# shield_v2.net
KiCad netlist of a schematic drawn in EAGLE
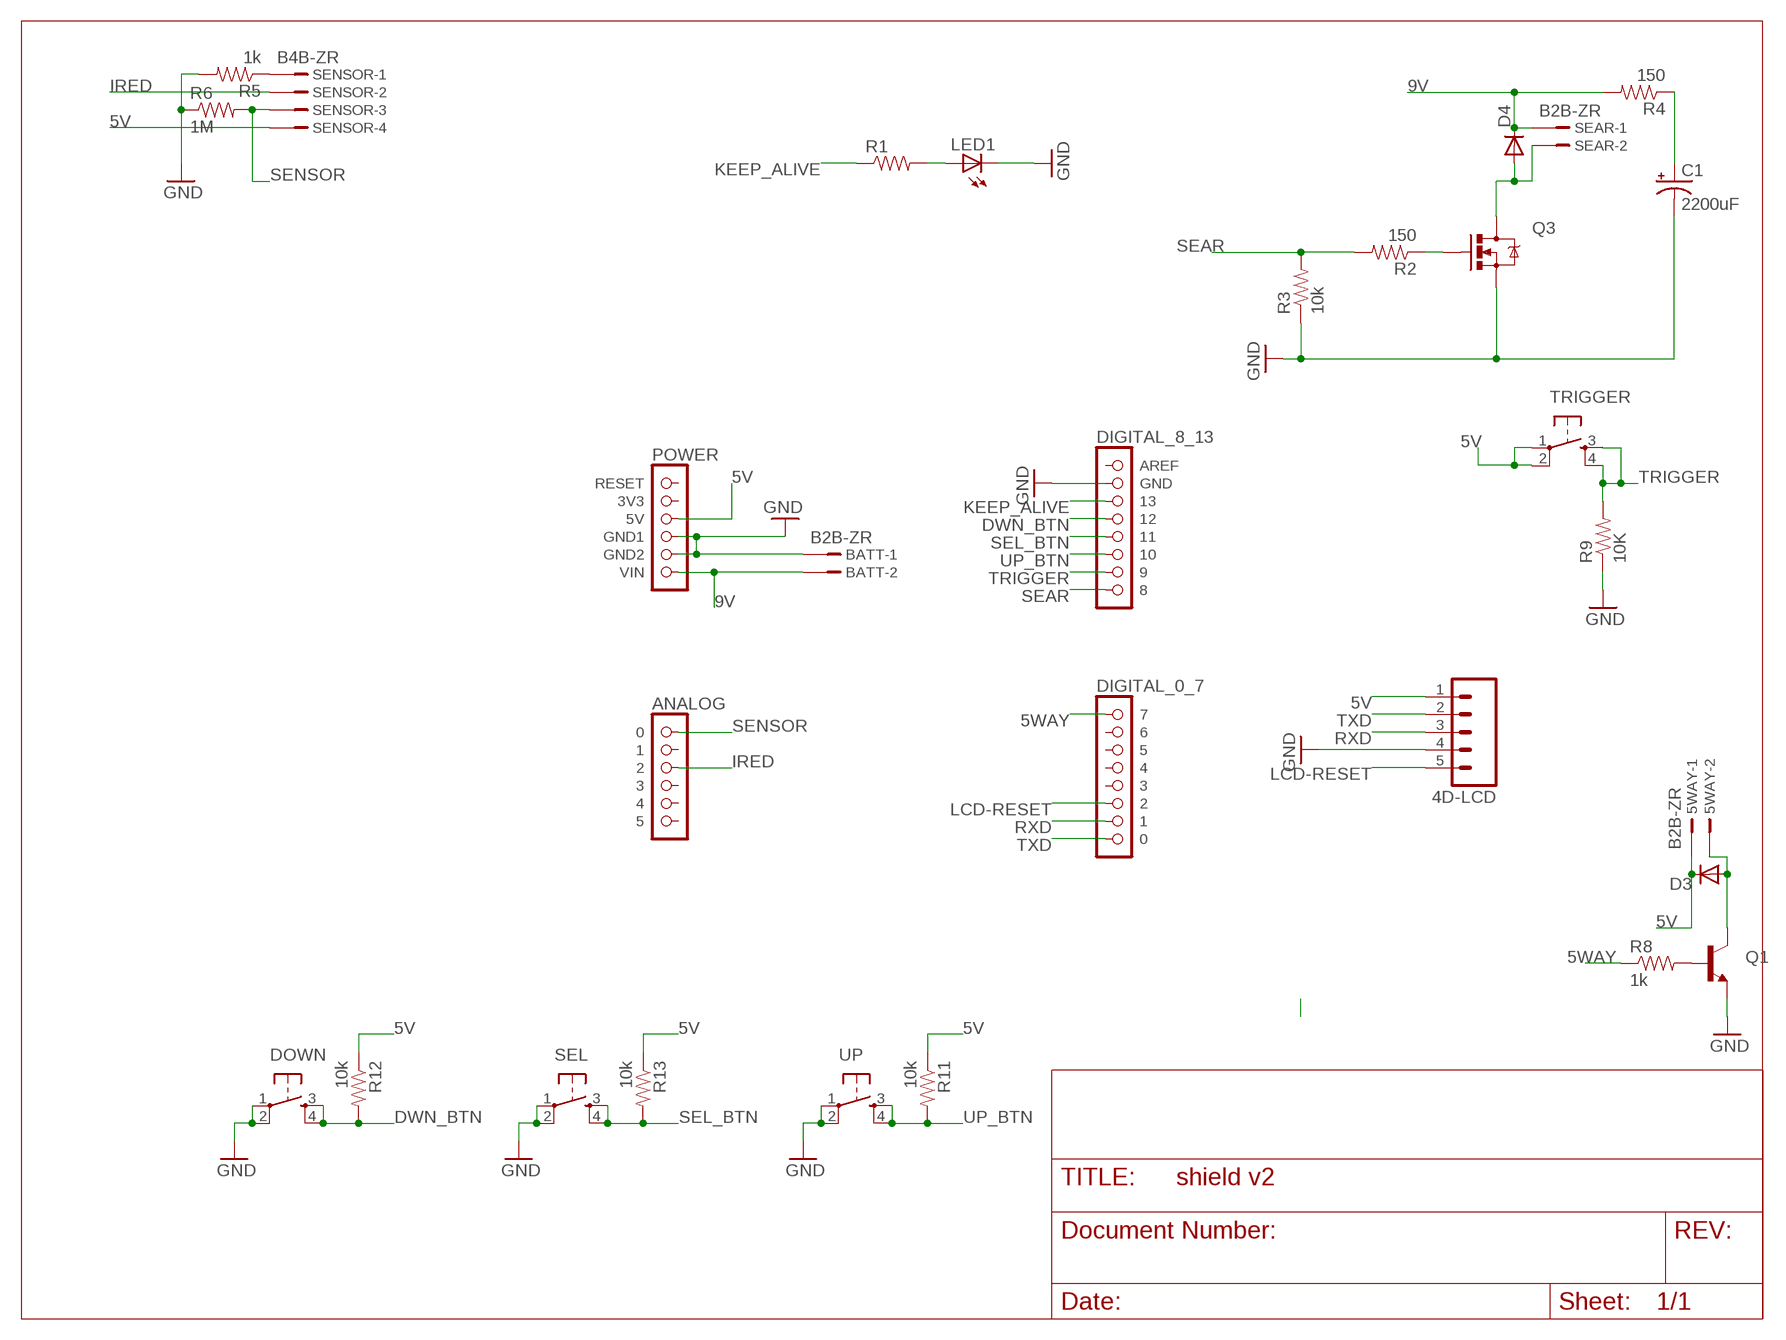
[diagram p0: schematic, sheet 1]

(export (version "E")
  (design (tool "Eeschema 10.0.6"))
  (components
    (comp (ref "4D-LCD")
      (value "M05PTH")
      (footprint "eagle-import:1X05")
      (libsource (lib "eagle-import") (part "M05PTH"))
    )
    (comp (ref "5WAY")
      (value "B2B-ZR")
      (footprint "eagle-import:B2B-ZR@1")
      (libsource (lib "eagle-import") (part "B2B-ZR"))
    )
    (comp (ref "BATT")
      (value "B2B-ZR")
      (footprint "eagle-import:B2B-ZR")
      (libsource (lib "eagle-import") (part "?2B-ZRB"))
    )
    (comp (ref "C1")
      (value "2200uF")
      (footprint "eagle-import:CPOL-RADIAL-1000UF-25V")
      (libsource (lib "eagle-import") (part "CAP_POLPTH4"))
    )
    (comp (ref "D3")
      (value "DIODEPTH")
      (footprint "eagle-import:DIODE-1N4001")
      (libsource (lib "eagle-import") (part "DIODEPTH"))
    )
    (comp (ref "D4")
      (value "DIODEPTH")
      (footprint "eagle-import:DIODE-1N4001")
      (libsource (lib "eagle-import") (part "DIODEPTH"))
    )
    (comp (ref "DOWN")
      (value "TAC_SWITCHPTH")
      (footprint "eagle-import:TACTILE-PTH")
      (libsource (lib "eagle-import") (part "TAC_SWITCHPTH"))
    )
    (comp (ref "LED1")
      (value "LED3MM")
      (footprint "eagle-import:LED3MM")
      (libsource (lib "eagle-import") (part "LED3MM"))
    )
    (comp (ref "Q1")
      (value "TRANSISTOR_NPNTO-92-AMMO")
      (footprint "eagle-import:TO-92-AMMO")
      (libsource (lib "eagle-import") (part "TRANSISTOR_NPNTO-92-AMMO"))
    )
    (comp (ref "Q3")
      (value "MOSFET-NCHANNELPTH2")
      (footprint "eagle-import:TO220V")
      (libsource (lib "eagle-import") (part "MOSFET-NCHANNELPTH2"))
    )
    (comp (ref "R1")
      (value "RESISTORPTH-1/4W")
      (footprint "eagle-import:AXIAL-0.4")
      (libsource (lib "eagle-import") (part "RESISTORPTH-1/4W"))
    )
    (comp (ref "R2")
      (value "150")
      (footprint "eagle-import:AXIAL-0.4")
      (libsource (lib "eagle-import") (part "RESISTORPTH-1/4W"))
    )
    (comp (ref "R3")
      (value "10k")
      (footprint "eagle-import:AXIAL-0.4")
      (libsource (lib "eagle-import") (part "RESISTORPTH-1/4W"))
    )
    (comp (ref "R4")
      (value "150")
      (footprint "eagle-import:AXIAL-0.4")
      (libsource (lib "eagle-import") (part "RESISTORPTH-1/4W"))
    )
    (comp (ref "R5")
      (value "1k")
      (footprint "eagle-import:AXIAL-0.4")
      (libsource (lib "eagle-import") (part "RESISTORPTH-1/4W"))
    )
    (comp (ref "R6")
      (value "1M")
      (footprint "eagle-import:AXIAL-0.4")
      (libsource (lib "eagle-import") (part "RESISTORPTH-1/4W"))
    )
    (comp (ref "R8")
      (value "1k")
      (footprint "eagle-import:AXIAL-0.4")
      (libsource (lib "eagle-import") (part "RESISTORPTH-1/4W"))
    )
    (comp (ref "R9")
      (value "10K")
      (footprint "eagle-import:AXIAL-0.4")
      (libsource (lib "eagle-import") (part "RESISTORPTH-1/4W"))
    )
    (comp (ref "R11")
      (value "10k")
      (footprint "eagle-import:AXIAL-0.4")
      (libsource (lib "eagle-import") (part "RESISTORPTH-1/4W"))
    )
    (comp (ref "R12")
      (value "10k")
      (footprint "eagle-import:AXIAL-0.4")
      (libsource (lib "eagle-import") (part "RESISTORPTH-1/4W"))
    )
    (comp (ref "R13")
      (value "10k")
      (footprint "eagle-import:AXIAL-0.4")
      (libsource (lib "eagle-import") (part "RESISTORPTH-1/4W"))
    )
    (comp (ref "SEAR")
      (value "B2B-ZR")
      (footprint "eagle-import:B2B-ZR@1")
      (libsource (lib "eagle-import") (part "B2B-ZR"))
    )
    (comp (ref "SEL")
      (value "TAC_SWITCHPTH")
      (footprint "eagle-import:TACTILE-PTH")
      (libsource (lib "eagle-import") (part "TAC_SWITCHPTH"))
    )
    (comp (ref "SENSOR")
      (value "B4B-ZR")
      (footprint "eagle-import:B4B-ZR")
      (fields (field (name "MF") "FARNELL") (field (name "MPN") "B4B-ZR(LF)(SN)"))
      (libsource (lib "eagle-import") (part "?4B-ZRB"))
    )
    (comp (ref "TRIGGER")
      (value "TAC_SWITCHPTH")
      (footprint "eagle-import:TACTILE-PTH")
      (libsource (lib "eagle-import") (part "TAC_SWITCHPTH"))
    )
    (comp (ref "U$1")
      (value "POWER")
      (footprint "eagle-import:1X06")
      (libsource (lib "eagle-import") (part "POWER"))
    )
    (comp (ref "U$2")
      (value "ANALOG")
      (footprint "eagle-import:1X06")
      (libsource (lib "eagle-import") (part "ANALOG"))
    )
    (comp (ref "U$3")
      (value "DIGITAL_0_7")
      (footprint "eagle-import:1X08")
      (libsource (lib "eagle-import") (part "DIGITAL_0_7"))
    )
    (comp (ref "U$4")
      (value "DIGITAL_8_13")
      (footprint "eagle-import:1X08")
      (libsource (lib "eagle-import") (part "DIGITAL_8_13"))
    )
    (comp (ref "UP")
      (value "TAC_SWITCHPTH")
      (footprint "eagle-import:TACTILE-PTH")
      (libsource (lib "eagle-import") (part "TAC_SWITCHPTH"))
    )
  )
  (nets
    (net (code "1") (name "/5V") (class "Default")
      (node (ref "4D-LCD") (pin "1") (pinfunction "1_1") (pintype "passive"))
      (node (ref "5WAY") (pin "1") (pinfunction "1_1") (pintype "passive"))
      (node (ref "D3") (pin "C") (pinfunction "C_C") (pintype "passive"))
      (node (ref "R11") (pin "P$1") (pinfunction "1_P$1") (pintype "passive"))
      (node (ref "R12") (pin "P$1") (pinfunction "1_P$1") (pintype "passive"))
      (node (ref "R13") (pin "P$1") (pinfunction "1_P$1") (pintype "passive"))
      (node (ref "SENSOR") (pin "4") (pinfunction "1_4") (pintype "passive"))
      (node (ref "TRIGGER") (pin "1") (pinfunction "1_1") (pintype "passive"))
      (node (ref "TRIGGER") (pin "2") (pinfunction "2_2") (pintype "passive"))
      (node (ref "U$1") (pin "3") (pinfunction "5V_3") (pintype "passive"))
    )
    (net (code "2") (name "/5WAY") (class "Default")
      (node (ref "R8") (pin "P$1") (pinfunction "1_P$1") (pintype "passive"))
      (node (ref "U$3") (pin "1") (pinfunction "7_1") (pintype "passive"))
    )
    (net (code "3") (name "/9V") (class "Default")
      (node (ref "BATT") (pin "2") (pinfunction "1_2") (pintype "passive"))
      (node (ref "D4") (pin "C") (pinfunction "C_C") (pintype "passive"))
      (node (ref "R4") (pin "P$2") (pinfunction "2_P$2") (pintype "passive"))
      (node (ref "SEAR") (pin "1") (pinfunction "1_1") (pintype "passive"))
      (node (ref "U$1") (pin "6") (pinfunction "VIN_6") (pintype "passive"))
    )
    (net (code "4") (name "/DWN_BTN") (class "Default")
      (node (ref "DOWN") (pin "3") (pinfunction "3_3") (pintype "passive"))
      (node (ref "DOWN") (pin "4") (pinfunction "4_4") (pintype "passive"))
      (node (ref "R12") (pin "P$2") (pinfunction "2_P$2") (pintype "passive"))
      (node (ref "U$4") (pin "4") (pinfunction "12_4") (pintype "passive"))
    )
    (net (code "5") (name "/IRED") (class "Default")
      (node (ref "SENSOR") (pin "2") (pinfunction "1_2") (pintype "passive"))
      (node (ref "U$2") (pin "3") (pinfunction "2_3") (pintype "passive"))
    )
    (net (code "6") (name "/KEEP_ALIVE") (class "Default")
      (node (ref "R1") (pin "P$1") (pinfunction "1_P$1") (pintype "passive"))
      (node (ref "U$4") (pin "3") (pinfunction "13_3") (pintype "passive"))
    )
    (net (code "7") (name "/LCD-RESET") (class "Default")
      (node (ref "4D-LCD") (pin "5") (pinfunction "5_5") (pintype "passive"))
      (node (ref "U$3") (pin "6") (pinfunction "2_6") (pintype "passive"))
    )
    (net (code "8") (name "/RXD") (class "Default")
      (node (ref "4D-LCD") (pin "3") (pinfunction "3_3") (pintype "passive"))
      (node (ref "U$3") (pin "7") (pinfunction "1_7") (pintype "passive"))
    )
    (net (code "9") (name "/SEAR") (class "Default")
      (node (ref "R2") (pin "P$2") (pinfunction "2_P$2") (pintype "passive"))
      (node (ref "R3") (pin "P$2") (pinfunction "2_P$2") (pintype "passive"))
      (node (ref "U$4") (pin "8") (pinfunction "8_8") (pintype "passive"))
    )
    (net (code "10") (name "/SEL_BTN") (class "Default")
      (node (ref "R13") (pin "P$2") (pinfunction "2_P$2") (pintype "passive"))
      (node (ref "SEL") (pin "3") (pinfunction "3_3") (pintype "passive"))
      (node (ref "SEL") (pin "4") (pinfunction "4_4") (pintype "passive"))
      (node (ref "U$4") (pin "5") (pinfunction "11_5") (pintype "passive"))
    )
    (net (code "11") (name "/SENSOR") (class "Default")
      (node (ref "R6") (pin "P$2") (pinfunction "2_P$2") (pintype "passive"))
      (node (ref "SENSOR") (pin "3") (pinfunction "1_3") (pintype "passive"))
      (node (ref "U$2") (pin "1") (pinfunction "0_1") (pintype "passive"))
    )
    (net (code "12") (name "/TRIGGER") (class "Default")
      (node (ref "R9") (pin "P$2") (pinfunction "2_P$2") (pintype "passive"))
      (node (ref "TRIGGER") (pin "3") (pinfunction "3_3") (pintype "passive"))
      (node (ref "TRIGGER") (pin "4") (pinfunction "4_4") (pintype "passive"))
      (node (ref "U$4") (pin "7") (pinfunction "9_7") (pintype "passive"))
    )
    (net (code "13") (name "/TXD") (class "Default")
      (node (ref "4D-LCD") (pin "2") (pinfunction "2_2") (pintype "passive"))
      (node (ref "U$3") (pin "8") (pinfunction "0_8") (pintype "passive"))
    )
    (net (code "14") (name "/UP_BTN") (class "Default")
      (node (ref "R11") (pin "P$2") (pinfunction "2_P$2") (pintype "passive"))
      (node (ref "U$4") (pin "6") (pinfunction "10_6") (pintype "passive"))
      (node (ref "UP") (pin "3") (pinfunction "3_3") (pintype "passive"))
      (node (ref "UP") (pin "4") (pinfunction "4_4") (pintype "passive"))
    )
    (net (code "15") (name "GND") (class "Default")
      (node (ref "4D-LCD") (pin "4") (pinfunction "4_4") (pintype "passive"))
      (node (ref "BATT") (pin "1") (pinfunction "1_1") (pintype "passive"))
      (node (ref "C1") (pin "2") (pinfunction "-_2") (pintype "passive"))
      (node (ref "DOWN") (pin "1") (pinfunction "1_1") (pintype "passive"))
      (node (ref "DOWN") (pin "2") (pinfunction "2_2") (pintype "passive"))
      (node (ref "LED1") (pin "K") (pinfunction "C_K") (pintype "passive"))
      (node (ref "Q1") (pin "1") (pinfunction "E_1") (pintype "passive"))
      (node (ref "Q3") (pin "3") (pinfunction "S_3") (pintype "passive"))
      (node (ref "R3") (pin "P$1") (pinfunction "1_P$1") (pintype "passive"))
      (node (ref "R5") (pin "P$2") (pinfunction "2_P$2") (pintype "passive"))
      (node (ref "R6") (pin "P$1") (pinfunction "1_P$1") (pintype "passive"))
      (node (ref "R9") (pin "P$1") (pinfunction "1_P$1") (pintype "passive"))
      (node (ref "SEL") (pin "1") (pinfunction "1_1") (pintype "passive"))
      (node (ref "SEL") (pin "2") (pinfunction "2_2") (pintype "passive"))
      (node (ref "U$1") (pin "4") (pinfunction "GND1_4") (pintype "passive"))
      (node (ref "U$1") (pin "5") (pinfunction "GND2_5") (pintype "passive"))
      (node (ref "U$4") (pin "2") (pinfunction "GND_2") (pintype "passive"))
      (node (ref "UP") (pin "1") (pinfunction "1_1") (pintype "passive"))
      (node (ref "UP") (pin "2") (pinfunction "2_2") (pintype "passive"))
    )
    (net (code "16") (name "Net-(5WAYB-1)") (class "Default")
      (node (ref "5WAY") (pin "2") (pinfunction "1_2") (pintype "passive"))
      (node (ref "D3") (pin "A") (pinfunction "A_A") (pintype "passive"))
      (node (ref "Q1") (pin "3") (pinfunction "C_3") (pintype "passive"))
    )
    (net (code "17") (name "Net-(C1-+)") (class "Default")
      (node (ref "C1") (pin "1") (pinfunction "+_1") (pintype "passive"))
      (node (ref "R4") (pin "P$1") (pinfunction "1_P$1") (pintype "passive"))
    )
    (net (code "18") (name "Net-(Q1-B)") (class "Default")
      (node (ref "Q1") (pin "2") (pinfunction "B_2") (pintype "passive"))
      (node (ref "R8") (pin "P$2") (pinfunction "2_P$2") (pintype "passive"))
    )
    (net (code "19") (name "Net-(Q3-D)") (class "Default")
      (node (ref "D4") (pin "A") (pinfunction "A_A") (pintype "passive"))
      (node (ref "Q3") (pin "2") (pinfunction "D_2") (pintype "passive"))
      (node (ref "SEAR") (pin "2") (pinfunction "1_2") (pintype "passive"))
    )
    (net (code "20") (name "Net-(Q3-G)") (class "Default")
      (node (ref "Q3") (pin "1") (pinfunction "G_1") (pintype "passive"))
      (node (ref "R2") (pin "P$1") (pinfunction "1_P$1") (pintype "passive"))
    )
    (net (code "21") (name "Net-(R1-2)") (class "Default")
      (node (ref "LED1") (pin "A") (pinfunction "A_A") (pintype "passive"))
      (node (ref "R1") (pin "P$2") (pinfunction "2_P$2") (pintype "passive"))
    )
    (net (code "22") (name "Net-(R5-1)") (class "Default")
      (node (ref "R5") (pin "P$1") (pinfunction "1_P$1") (pintype "passive"))
      (node (ref "SENSOR") (pin "1") (pinfunction "1_1") (pintype "passive"))
    )
    (net (code "23") (name "unconnected-(U$1-3V3-Pad2)") (class "Default")
      (node (ref "U$1") (pin "2") (pinfunction "3V3_2") (pintype "passive"))
    )
    (net (code "24") (name "unconnected-(U$1-RESET-Pad1)") (class "Default")
      (node (ref "U$1") (pin "1") (pinfunction "RESET_1") (pintype "passive"))
    )
    (net (code "25") (name "unconnected-(U$2-1-Pad2)") (class "Default")
      (node (ref "U$2") (pin "2") (pinfunction "1_2") (pintype "passive"))
    )
    (net (code "26") (name "unconnected-(U$2-3-Pad4)") (class "Default")
      (node (ref "U$2") (pin "4") (pinfunction "3_4") (pintype "passive"))
    )
    (net (code "27") (name "unconnected-(U$2-4-Pad5)") (class "Default")
      (node (ref "U$2") (pin "5") (pinfunction "4_5") (pintype "passive"))
    )
    (net (code "28") (name "unconnected-(U$2-5-Pad6)") (class "Default")
      (node (ref "U$2") (pin "6") (pinfunction "5_6") (pintype "passive"))
    )
    (net (code "29") (name "unconnected-(U$3-3-Pad5)") (class "Default")
      (node (ref "U$3") (pin "5") (pinfunction "3_5") (pintype "passive"))
    )
    (net (code "30") (name "unconnected-(U$3-5-Pad3)") (class "Default")
      (node (ref "U$3") (pin "3") (pinfunction "5_3") (pintype "passive"))
    )
    (net (code "31") (name "unconnected-(U$3-6-Pad2)") (class "Default")
      (node (ref "U$3") (pin "2") (pinfunction "6_2") (pintype "passive"))
    )
    (net (code "32") (name "unconnected-(U$3-Pad4)") (class "Default")
      (node (ref "U$3") (pin "4") (pinfunction "4_4") (pintype "passive"))
    )
    (net (code "33") (name "unconnected-(U$4-AREF-Pad1)") (class "Default")
      (node (ref "U$4") (pin "1") (pinfunction "AREF_1") (pintype "passive"))
    )
  )
)
